# basic-thermometer_TH.net
KiCad netlist of a schematic drawn in EAGLE
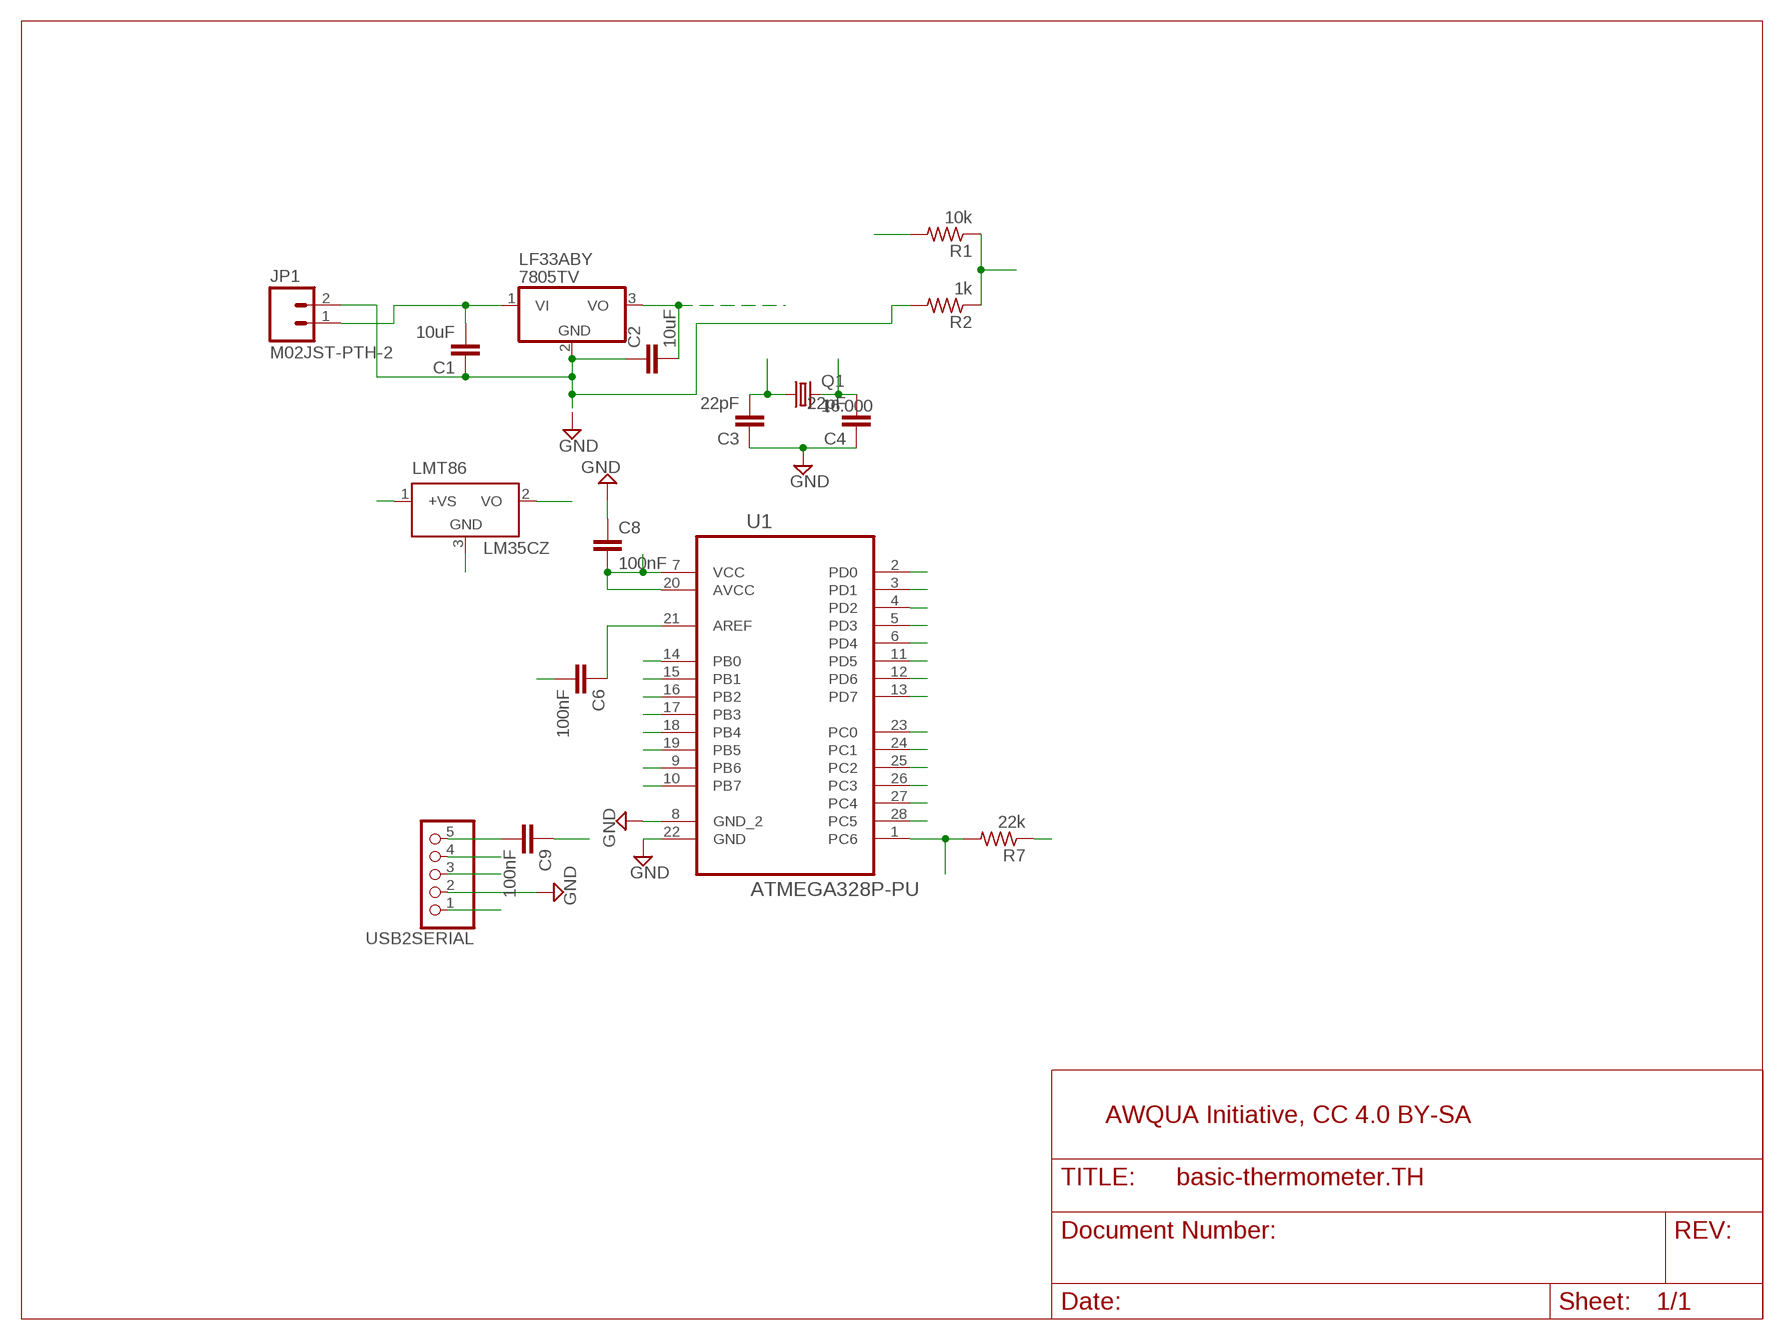
[diagram p0: schematic, sheet 1]

(export (version "E")
  (design (tool "Eeschema 10.0.6"))
  (components
    (comp (ref "C1")
      (value "10uF")
      (footprint "eagle-import:CAP-PTH-SMALLEZ")
      (libsource (lib "eagle-import") (part "CAPEZ"))
    )
    (comp (ref "C2")
      (value "10uF")
      (footprint "eagle-import:CAP-PTH-SMALLEZ")
      (libsource (lib "eagle-import") (part "CAPEZ"))
    )
    (comp (ref "C3")
      (value "22pF")
      (footprint "eagle-import:CAP-PTH-SMALLEZ")
      (libsource (lib "eagle-import") (part "CAPEZ"))
    )
    (comp (ref "C4")
      (value "22pF")
      (footprint "eagle-import:CAP-PTH-SMALLEZ")
      (libsource (lib "eagle-import") (part "CAPEZ"))
    )
    (comp (ref "C6")
      (value "100nF")
      (footprint "eagle-import:CAP-PTH-SMALLEZ")
      (libsource (lib "eagle-import") (part "CAPEZ"))
    )
    (comp (ref "C8")
      (value "100nF")
      (footprint "eagle-import:CAP-PTH-SMALLEZ")
      (libsource (lib "eagle-import") (part "CAPEZ"))
    )
    (comp (ref "C9")
      (value "100nF")
      (footprint "eagle-import:CAP-PTH-SMALLEZ")
      (libsource (lib "eagle-import") (part "CAPEZ"))
    )
    (comp (ref "JP1")
      (value "M02JST-PTH-2")
      (footprint "eagle-import:JST-2-PTH")
      (libsource (lib "eagle-import") (part "M02JST-PTH-2"))
    )
    (comp (ref "LF33ABY")
      (value "7805TV")
      (footprint "eagle-import:TO220V")
      (libsource (lib "eagle-import") (part "78TV05"))
    )
    (comp (ref "LMT86")
      (value "LM35CZ")
      (footprint "eagle-import:TO92")
      (libsource (lib "eagle-import") (part "LM35CZ"))
    )
    (comp (ref "Q1")
      (value "16.000")
      (footprint "eagle-import:HC49_S")
      (libsource (lib "eagle-import") (part "CRYSTALHC49S"))
    )
    (comp (ref "R1")
      (value "10k")
      (footprint "eagle-import:0204_7")
      (libsource (lib "eagle-import") (part "R-US_0204/7"))
    )
    (comp (ref "R2")
      (value "1k")
      (footprint "eagle-import:0204_7")
      (libsource (lib "eagle-import") (part "R-US_0204/7"))
    )
    (comp (ref "R7")
      (value "22k")
      (footprint "eagle-import:0204_7")
      (libsource (lib "eagle-import") (part "R-US_0204/7"))
    )
    (comp (ref "U1")
      (value "ATMEGA328P-PU")
      (footprint "eagle-import:DIP254P762X457-28")
      (libsource (lib "eagle-import") (part "ATMEGA328P-PU"))
    )
    (comp (ref "USB2SERIAL")
      (value "PINHD-1X5")
      (footprint "eagle-import:1X05")
      (libsource (lib "eagle-import") (part "PINHD-1X5"))
    )
  )
  (nets
    (net (code "1") (name "/3V3") (class "Default")
      (node (ref "C2") (pin "2") (pinfunction "2_2") (pintype "passive"))
      (node (ref "C8") (pin "2") (pinfunction "2_2") (pintype "passive"))
      (node (ref "LF33ABY") (pin "3") (pinfunction "VO_3") (pintype "passive"))
      (node (ref "LMT86") (pin "1") (pinfunction "+VS_1") (pintype "input"))
      (node (ref "R1") (pin "2") (pinfunction "2_2") (pintype "passive"))
      (node (ref "R7") (pin "1") (pinfunction "1_1") (pintype "passive"))
      (node (ref "U1") (pin "20") (pinfunction "AVCC_20") (pintype "power_in"))
      (node (ref "U1") (pin "7") (pinfunction "VCC_7") (pintype "power_in"))
      (node (ref "USB2SERIAL") (pin "1") (pinfunction "1_1") (pintype "passive"))
    )
    (net (code "2") (name "/PB6") (class "Default")
      (node (ref "C3") (pin "2") (pinfunction "2_2") (pintype "passive"))
      (node (ref "Q1") (pin "1") (pinfunction "1_1") (pintype "passive"))
      (node (ref "U1") (pin "9") (pinfunction "PB6_9") (pintype "bidirectional"))
    )
    (net (code "3") (name "/PB7") (class "Default")
      (node (ref "C4") (pin "2") (pinfunction "2_2") (pintype "passive"))
      (node (ref "Q1") (pin "2") (pinfunction "2_2") (pintype "passive"))
      (node (ref "U1") (pin "10") (pinfunction "PB7_10") (pintype "bidirectional"))
    )
    (net (code "4") (name "/PC0") (class "Default")
      (node (ref "LMT86") (pin "2") (pinfunction "VO_2") (pintype "input"))
      (node (ref "U1") (pin "23") (pinfunction "PC0_23") (pintype "bidirectional"))
    )
    (net (code "5") (name "/PC4") (class "Default")
      (node (ref "R1") (pin "1") (pinfunction "1_1") (pintype "passive"))
      (node (ref "R2") (pin "1") (pinfunction "1_1") (pintype "passive"))
      (node (ref "U1") (pin "27") (pinfunction "PC4_27") (pintype "bidirectional"))
    )
    (net (code "6") (name "/PC6") (class "Default")
      (node (ref "C9") (pin "1") (pinfunction "1_1") (pintype "passive"))
      (node (ref "R7") (pin "2") (pinfunction "2_2") (pintype "passive"))
      (node (ref "U1") (pin "1") (pinfunction "PC6_1") (pintype "bidirectional"))
    )
    (net (code "7") (name "/PD0") (class "Default")
      (node (ref "U1") (pin "2") (pinfunction "PD0_2") (pintype "bidirectional"))
      (node (ref "USB2SERIAL") (pin "3") (pinfunction "3_3") (pintype "passive"))
    )
    (net (code "8") (name "/PD1") (class "Default")
      (node (ref "U1") (pin "3") (pinfunction "PD1_3") (pintype "bidirectional"))
      (node (ref "USB2SERIAL") (pin "4") (pinfunction "4_4") (pintype "passive"))
    )
    (net (code "9") (name "GND") (class "Default")
      (node (ref "C1") (pin "1") (pinfunction "1_1") (pintype "passive"))
      (node (ref "C2") (pin "1") (pinfunction "1_1") (pintype "passive"))
      (node (ref "C3") (pin "1") (pinfunction "1_1") (pintype "passive"))
      (node (ref "C4") (pin "1") (pinfunction "1_1") (pintype "passive"))
      (node (ref "C6") (pin "2") (pinfunction "2_2") (pintype "passive"))
      (node (ref "C8") (pin "1") (pinfunction "1_1") (pintype "passive"))
      (node (ref "JP1") (pin "2") (pinfunction "2_2") (pintype "passive"))
      (node (ref "LF33ABY") (pin "2") (pinfunction "GND_2") (pintype "passive"))
      (node (ref "LMT86") (pin "3") (pinfunction "GND_3") (pintype "power_in"))
      (node (ref "R2") (pin "2") (pinfunction "2_2") (pintype "passive"))
      (node (ref "U1") (pin "13") (pinfunction "PD7_13") (pintype "bidirectional"))
      (node (ref "U1") (pin "22") (pinfunction "GND_22") (pintype "passive"))
      (node (ref "U1") (pin "5") (pinfunction "PD3_5") (pintype "bidirectional"))
      (node (ref "U1") (pin "8") (pinfunction "GND_2_8") (pintype "passive"))
      (node (ref "USB2SERIAL") (pin "2") (pinfunction "2_2") (pintype "passive"))
    )
    (net (code "10") (name "Net-(C9-Pad2)") (class "Default")
      (node (ref "C9") (pin "2") (pinfunction "2_2") (pintype "passive"))
      (node (ref "USB2SERIAL") (pin "5") (pinfunction "5_5") (pintype "passive"))
    )
    (net (code "11") (name "Net-(LF33ABY-VI)") (class "Default")
      (node (ref "C1") (pin "2") (pinfunction "2_2") (pintype "passive"))
      (node (ref "JP1") (pin "1") (pinfunction "1_1") (pintype "passive"))
      (node (ref "LF33ABY") (pin "1") (pinfunction "VI_1") (pintype "input"))
    )
    (net (code "12") (name "Net-(U1-AREF)") (class "Default")
      (node (ref "C6") (pin "1") (pinfunction "1_1") (pintype "passive"))
      (node (ref "U1") (pin "21") (pinfunction "AREF_21") (pintype "input"))
    )
    (net (code "13") (name "unconnected-(U1-PB0-Pad14)") (class "Default")
      (node (ref "U1") (pin "14") (pinfunction "PB0_14") (pintype "bidirectional"))
    )
    (net (code "14") (name "unconnected-(U1-PB1-Pad15)") (class "Default")
      (node (ref "U1") (pin "15") (pinfunction "PB1_15") (pintype "bidirectional"))
    )
    (net (code "15") (name "unconnected-(U1-PB2-Pad16)") (class "Default")
      (node (ref "U1") (pin "16") (pinfunction "PB2_16") (pintype "bidirectional"))
    )
    (net (code "16") (name "unconnected-(U1-PB3-Pad17)") (class "Default")
      (node (ref "U1") (pin "17") (pinfunction "PB3_17") (pintype "bidirectional"))
    )
    (net (code "17") (name "unconnected-(U1-PB4-Pad18)") (class "Default")
      (node (ref "U1") (pin "18") (pinfunction "PB4_18") (pintype "bidirectional"))
    )
    (net (code "18") (name "unconnected-(U1-PB5-Pad19)") (class "Default")
      (node (ref "U1") (pin "19") (pinfunction "PB5_19") (pintype "bidirectional"))
    )
    (net (code "19") (name "unconnected-(U1-PC1-Pad24)") (class "Default")
      (node (ref "U1") (pin "24") (pinfunction "PC1_24") (pintype "bidirectional"))
    )
    (net (code "20") (name "unconnected-(U1-PC2-Pad25)") (class "Default")
      (node (ref "U1") (pin "25") (pinfunction "PC2_25") (pintype "bidirectional"))
    )
    (net (code "21") (name "unconnected-(U1-PC3-Pad26)") (class "Default")
      (node (ref "U1") (pin "26") (pinfunction "PC3_26") (pintype "bidirectional"))
    )
    (net (code "22") (name "unconnected-(U1-PC5-Pad28)") (class "Default")
      (node (ref "U1") (pin "28") (pinfunction "PC5_28") (pintype "bidirectional"))
    )
    (net (code "23") (name "unconnected-(U1-PD2-Pad4)") (class "Default")
      (node (ref "U1") (pin "4") (pinfunction "PD2_4") (pintype "bidirectional"))
    )
    (net (code "24") (name "unconnected-(U1-PD4-Pad6)") (class "Default")
      (node (ref "U1") (pin "6") (pinfunction "PD4_6") (pintype "bidirectional"))
    )
    (net (code "25") (name "unconnected-(U1-PD5-Pad11)") (class "Default")
      (node (ref "U1") (pin "11") (pinfunction "PD5_11") (pintype "bidirectional"))
    )
    (net (code "26") (name "unconnected-(U1-PD6-Pad12)") (class "Default")
      (node (ref "U1") (pin "12") (pinfunction "PD6_12") (pintype "bidirectional"))
    )
  )
)
